# schema.net
KiCad netlist of a schematic drawn in EAGLE
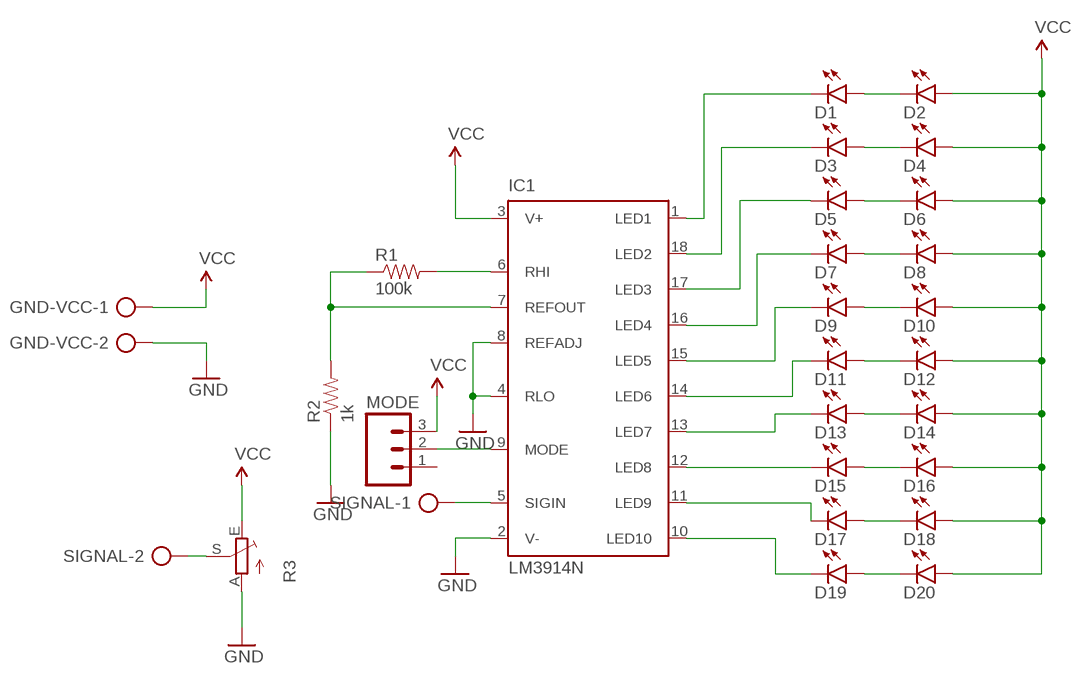
[diagram p0: schematic, sheet 1]

(export (version "E")
  (design (tool "Eeschema 10.0.6"))
  (components
    (comp (ref "D1")
      (value "LED5MM")
      (footprint "eagle-import:LED5MM")
      (libsource (lib "eagle-import") (part "LED5MM"))
    )
    (comp (ref "D2")
      (value "LED5MM")
      (footprint "eagle-import:LED5MM")
      (libsource (lib "eagle-import") (part "LED5MM"))
    )
    (comp (ref "D3")
      (value "LED5MM")
      (footprint "eagle-import:LED5MM")
      (libsource (lib "eagle-import") (part "LED5MM"))
    )
    (comp (ref "D4")
      (value "LED5MM")
      (footprint "eagle-import:LED5MM")
      (libsource (lib "eagle-import") (part "LED5MM"))
    )
    (comp (ref "D5")
      (value "LED5MM")
      (footprint "eagle-import:LED5MM")
      (libsource (lib "eagle-import") (part "LED5MM"))
    )
    (comp (ref "D6")
      (value "LED5MM")
      (footprint "eagle-import:LED5MM")
      (libsource (lib "eagle-import") (part "LED5MM"))
    )
    (comp (ref "D7")
      (value "LED5MM")
      (footprint "eagle-import:LED5MM")
      (libsource (lib "eagle-import") (part "LED5MM"))
    )
    (comp (ref "D8")
      (value "LED5MM")
      (footprint "eagle-import:LED5MM")
      (libsource (lib "eagle-import") (part "LED5MM"))
    )
    (comp (ref "D9")
      (value "LED5MM")
      (footprint "eagle-import:LED5MM")
      (libsource (lib "eagle-import") (part "LED5MM"))
    )
    (comp (ref "D10")
      (value "LED5MM")
      (footprint "eagle-import:LED5MM")
      (libsource (lib "eagle-import") (part "LED5MM"))
    )
    (comp (ref "D11")
      (value "LED5MM")
      (footprint "eagle-import:LED5MM")
      (libsource (lib "eagle-import") (part "LED5MM"))
    )
    (comp (ref "D12")
      (value "LED5MM")
      (footprint "eagle-import:LED5MM")
      (libsource (lib "eagle-import") (part "LED5MM"))
    )
    (comp (ref "D13")
      (value "LED5MM")
      (footprint "eagle-import:LED5MM")
      (libsource (lib "eagle-import") (part "LED5MM"))
    )
    (comp (ref "D14")
      (value "LED5MM")
      (footprint "eagle-import:LED5MM")
      (libsource (lib "eagle-import") (part "LED5MM"))
    )
    (comp (ref "D15")
      (value "LED5MM")
      (footprint "eagle-import:LED5MM")
      (libsource (lib "eagle-import") (part "LED5MM"))
    )
    (comp (ref "D16")
      (value "LED5MM")
      (footprint "eagle-import:LED5MM")
      (libsource (lib "eagle-import") (part "LED5MM"))
    )
    (comp (ref "D17")
      (value "LED5MM")
      (footprint "eagle-import:LED5MM")
      (libsource (lib "eagle-import") (part "LED5MM"))
    )
    (comp (ref "D18")
      (value "LED5MM")
      (footprint "eagle-import:LED5MM")
      (libsource (lib "eagle-import") (part "LED5MM"))
    )
    (comp (ref "D19")
      (value "LED5MM")
      (footprint "eagle-import:LED5MM")
      (libsource (lib "eagle-import") (part "LED5MM"))
    )
    (comp (ref "D20")
      (value "LED5MM")
      (footprint "eagle-import:LED5MM")
      (libsource (lib "eagle-import") (part "LED5MM"))
    )
    (comp (ref "GND-VCC")
      (value "AK500/2")
      (footprint "eagle-import:AK500_2")
      (libsource (lib "eagle-import") (part "AK500/2"))
    )
    (comp (ref "IC1")
      (value "LM3914N")
      (footprint "eagle-import:DIL18")
      (libsource (lib "eagle-import") (part "LM391N4"))
    )
    (comp (ref "MODE")
      (value "M03LONGPADS")
      (footprint "eagle-import:1X03_LONGPADS")
      (libsource (lib "eagle-import") (part "M03LONGPADS"))
    )
    (comp (ref "R1")
      (value "100k")
      (footprint "eagle-import:AXIAL-0.3-KIT")
      (libsource (lib "eagle-import") (part "RESISTORKIT"))
    )
    (comp (ref "R2")
      (value "1k")
      (footprint "eagle-import:AXIAL-0.3-KIT")
      (libsource (lib "eagle-import") (part "RESISTORKIT"))
    )
    (comp (ref "R3")
      (value "TRIM_EU-CA14H")
      (footprint "eagle-import:CA14H")
      (libsource (lib "eagle-import") (part "TRIM_EU-CA14H"))
    )
    (comp (ref "SIGNAL")
      (value "AK500/2")
      (footprint "eagle-import:AK500_2")
      (libsource (lib "eagle-import") (part "AK500/2"))
    )
  )
  (nets
    (net (code "1") (name "GND") (class "Default")
      (node (ref "GND-VCC") (pin "2") (pinfunction "KL_2") (pintype "passive"))
      (node (ref "IC1") (pin "2") (pinfunction "V-_2") (pintype "power_in"))
      (node (ref "IC1") (pin "4") (pinfunction "RLO_4") (pintype "input"))
      (node (ref "IC1") (pin "8") (pinfunction "REFADJ_8") (pintype "passive"))
      (node (ref "R2") (pin "P$1") (pinfunction "1_P$1") (pintype "passive"))
      (node (ref "R3") (pin "A") (pinfunction "A_A") (pintype "passive"))
    )
    (net (code "2") (name "Net-(D1-C)") (class "Default")
      (node (ref "D1") (pin "K") (pinfunction "C_K") (pintype "passive"))
      (node (ref "IC1") (pin "1") (pinfunction "LED1_1") (pintype "output"))
    )
    (net (code "3") (name "Net-(D2-C)") (class "Default")
      (node (ref "D1") (pin "A") (pinfunction "A_A") (pintype "passive"))
      (node (ref "D2") (pin "K") (pinfunction "C_K") (pintype "passive"))
    )
    (net (code "4") (name "Net-(D3-C)") (class "Default")
      (node (ref "D3") (pin "K") (pinfunction "C_K") (pintype "passive"))
      (node (ref "IC1") (pin "18") (pinfunction "LED2_18") (pintype "output"))
    )
    (net (code "5") (name "Net-(D4-C)") (class "Default")
      (node (ref "D3") (pin "A") (pinfunction "A_A") (pintype "passive"))
      (node (ref "D4") (pin "K") (pinfunction "C_K") (pintype "passive"))
    )
    (net (code "6") (name "Net-(D5-C)") (class "Default")
      (node (ref "D5") (pin "K") (pinfunction "C_K") (pintype "passive"))
      (node (ref "IC1") (pin "17") (pinfunction "LED3_17") (pintype "output"))
    )
    (net (code "7") (name "Net-(D6-C)") (class "Default")
      (node (ref "D5") (pin "A") (pinfunction "A_A") (pintype "passive"))
      (node (ref "D6") (pin "K") (pinfunction "C_K") (pintype "passive"))
    )
    (net (code "8") (name "Net-(D7-C)") (class "Default")
      (node (ref "D7") (pin "K") (pinfunction "C_K") (pintype "passive"))
      (node (ref "IC1") (pin "16") (pinfunction "LED4_16") (pintype "output"))
    )
    (net (code "9") (name "Net-(D8-C)") (class "Default")
      (node (ref "D7") (pin "A") (pinfunction "A_A") (pintype "passive"))
      (node (ref "D8") (pin "K") (pinfunction "C_K") (pintype "passive"))
    )
    (net (code "10") (name "Net-(D9-C)") (class "Default")
      (node (ref "D9") (pin "K") (pinfunction "C_K") (pintype "passive"))
      (node (ref "IC1") (pin "15") (pinfunction "LED5_15") (pintype "output"))
    )
    (net (code "11") (name "Net-(D10-C)") (class "Default")
      (node (ref "D10") (pin "K") (pinfunction "C_K") (pintype "passive"))
      (node (ref "D9") (pin "A") (pinfunction "A_A") (pintype "passive"))
    )
    (net (code "12") (name "Net-(D11-C)") (class "Default")
      (node (ref "D11") (pin "K") (pinfunction "C_K") (pintype "passive"))
      (node (ref "IC1") (pin "14") (pinfunction "LED6_14") (pintype "output"))
    )
    (net (code "13") (name "Net-(D12-C)") (class "Default")
      (node (ref "D11") (pin "A") (pinfunction "A_A") (pintype "passive"))
      (node (ref "D12") (pin "K") (pinfunction "C_K") (pintype "passive"))
    )
    (net (code "14") (name "Net-(D13-C)") (class "Default")
      (node (ref "D13") (pin "K") (pinfunction "C_K") (pintype "passive"))
      (node (ref "IC1") (pin "13") (pinfunction "LED7_13") (pintype "output"))
    )
    (net (code "15") (name "Net-(D14-C)") (class "Default")
      (node (ref "D13") (pin "A") (pinfunction "A_A") (pintype "passive"))
      (node (ref "D14") (pin "K") (pinfunction "C_K") (pintype "passive"))
    )
    (net (code "16") (name "Net-(D15-C)") (class "Default")
      (node (ref "D15") (pin "K") (pinfunction "C_K") (pintype "passive"))
      (node (ref "IC1") (pin "12") (pinfunction "LED8_12") (pintype "output"))
    )
    (net (code "17") (name "Net-(D16-C)") (class "Default")
      (node (ref "D15") (pin "A") (pinfunction "A_A") (pintype "passive"))
      (node (ref "D16") (pin "K") (pinfunction "C_K") (pintype "passive"))
    )
    (net (code "18") (name "Net-(D17-C)") (class "Default")
      (node (ref "D17") (pin "K") (pinfunction "C_K") (pintype "passive"))
      (node (ref "IC1") (pin "11") (pinfunction "LED9_11") (pintype "output"))
    )
    (net (code "19") (name "Net-(D18-C)") (class "Default")
      (node (ref "D17") (pin "A") (pinfunction "A_A") (pintype "passive"))
      (node (ref "D18") (pin "K") (pinfunction "C_K") (pintype "passive"))
    )
    (net (code "20") (name "Net-(D19-C)") (class "Default")
      (node (ref "D19") (pin "K") (pinfunction "C_K") (pintype "passive"))
      (node (ref "IC1") (pin "10") (pinfunction "LED10_10") (pintype "output"))
    )
    (net (code "21") (name "Net-(D20-C)") (class "Default")
      (node (ref "D19") (pin "A") (pinfunction "A_A") (pintype "passive"))
      (node (ref "D20") (pin "K") (pinfunction "C_K") (pintype "passive"))
    )
    (net (code "22") (name "Net-(IC1-MODE)") (class "Default")
      (node (ref "IC1") (pin "9") (pinfunction "MODE_9") (pintype "input"))
      (node (ref "MODE") (pin "2") (pinfunction "2_2") (pintype "passive"))
    )
    (net (code "23") (name "Net-(IC1-REFOUT)") (class "Default")
      (node (ref "IC1") (pin "7") (pinfunction "REFOUT_7") (pintype "output"))
      (node (ref "R1") (pin "P$1") (pinfunction "1_P$1") (pintype "passive"))
      (node (ref "R2") (pin "P$2") (pinfunction "2_P$2") (pintype "passive"))
    )
    (net (code "24") (name "Net-(IC1-RHI)") (class "Default")
      (node (ref "IC1") (pin "6") (pinfunction "RHI_6") (pintype "input"))
      (node (ref "R1") (pin "P$2") (pinfunction "2_P$2") (pintype "passive"))
    )
    (net (code "25") (name "Net-(IC1-SIGIN)") (class "Default")
      (node (ref "IC1") (pin "5") (pinfunction "SIGIN_5") (pintype "input"))
      (node (ref "SIGNAL") (pin "1") (pinfunction "KL_1") (pintype "passive"))
    )
    (net (code "26") (name "Net-(SIGNALB-KL)") (class "Default")
      (node (ref "R3") (pin "S") (pinfunction "S_S") (pintype "passive"))
      (node (ref "SIGNAL") (pin "2") (pinfunction "KL_2") (pintype "passive"))
    )
    (net (code "27") (name "VCC") (class "Default")
      (node (ref "D10") (pin "A") (pinfunction "A_A") (pintype "passive"))
      (node (ref "D12") (pin "A") (pinfunction "A_A") (pintype "passive"))
      (node (ref "D14") (pin "A") (pinfunction "A_A") (pintype "passive"))
      (node (ref "D16") (pin "A") (pinfunction "A_A") (pintype "passive"))
      (node (ref "D18") (pin "A") (pinfunction "A_A") (pintype "passive"))
      (node (ref "D2") (pin "A") (pinfunction "A_A") (pintype "passive"))
      (node (ref "D20") (pin "A") (pinfunction "A_A") (pintype "passive"))
      (node (ref "D4") (pin "A") (pinfunction "A_A") (pintype "passive"))
      (node (ref "D6") (pin "A") (pinfunction "A_A") (pintype "passive"))
      (node (ref "D8") (pin "A") (pinfunction "A_A") (pintype "passive"))
      (node (ref "GND-VCC") (pin "1") (pinfunction "KL_1") (pintype "passive"))
      (node (ref "IC1") (pin "3") (pinfunction "V+_3") (pintype "power_in"))
      (node (ref "MODE") (pin "3") (pinfunction "3_3") (pintype "passive"))
      (node (ref "R3") (pin "E") (pinfunction "E_E") (pintype "passive"))
    )
    (net (code "28") (name "unconnected-(MODE-Pad1)") (class "Default")
      (node (ref "MODE") (pin "1") (pinfunction "1_1") (pintype "passive"))
    )
  )
)
